# VRAM_SIMM_TC5262x7J_v1_0_Sch_EasyEDA.net
KiCad netlist of a schematic drawn in EasyEDA
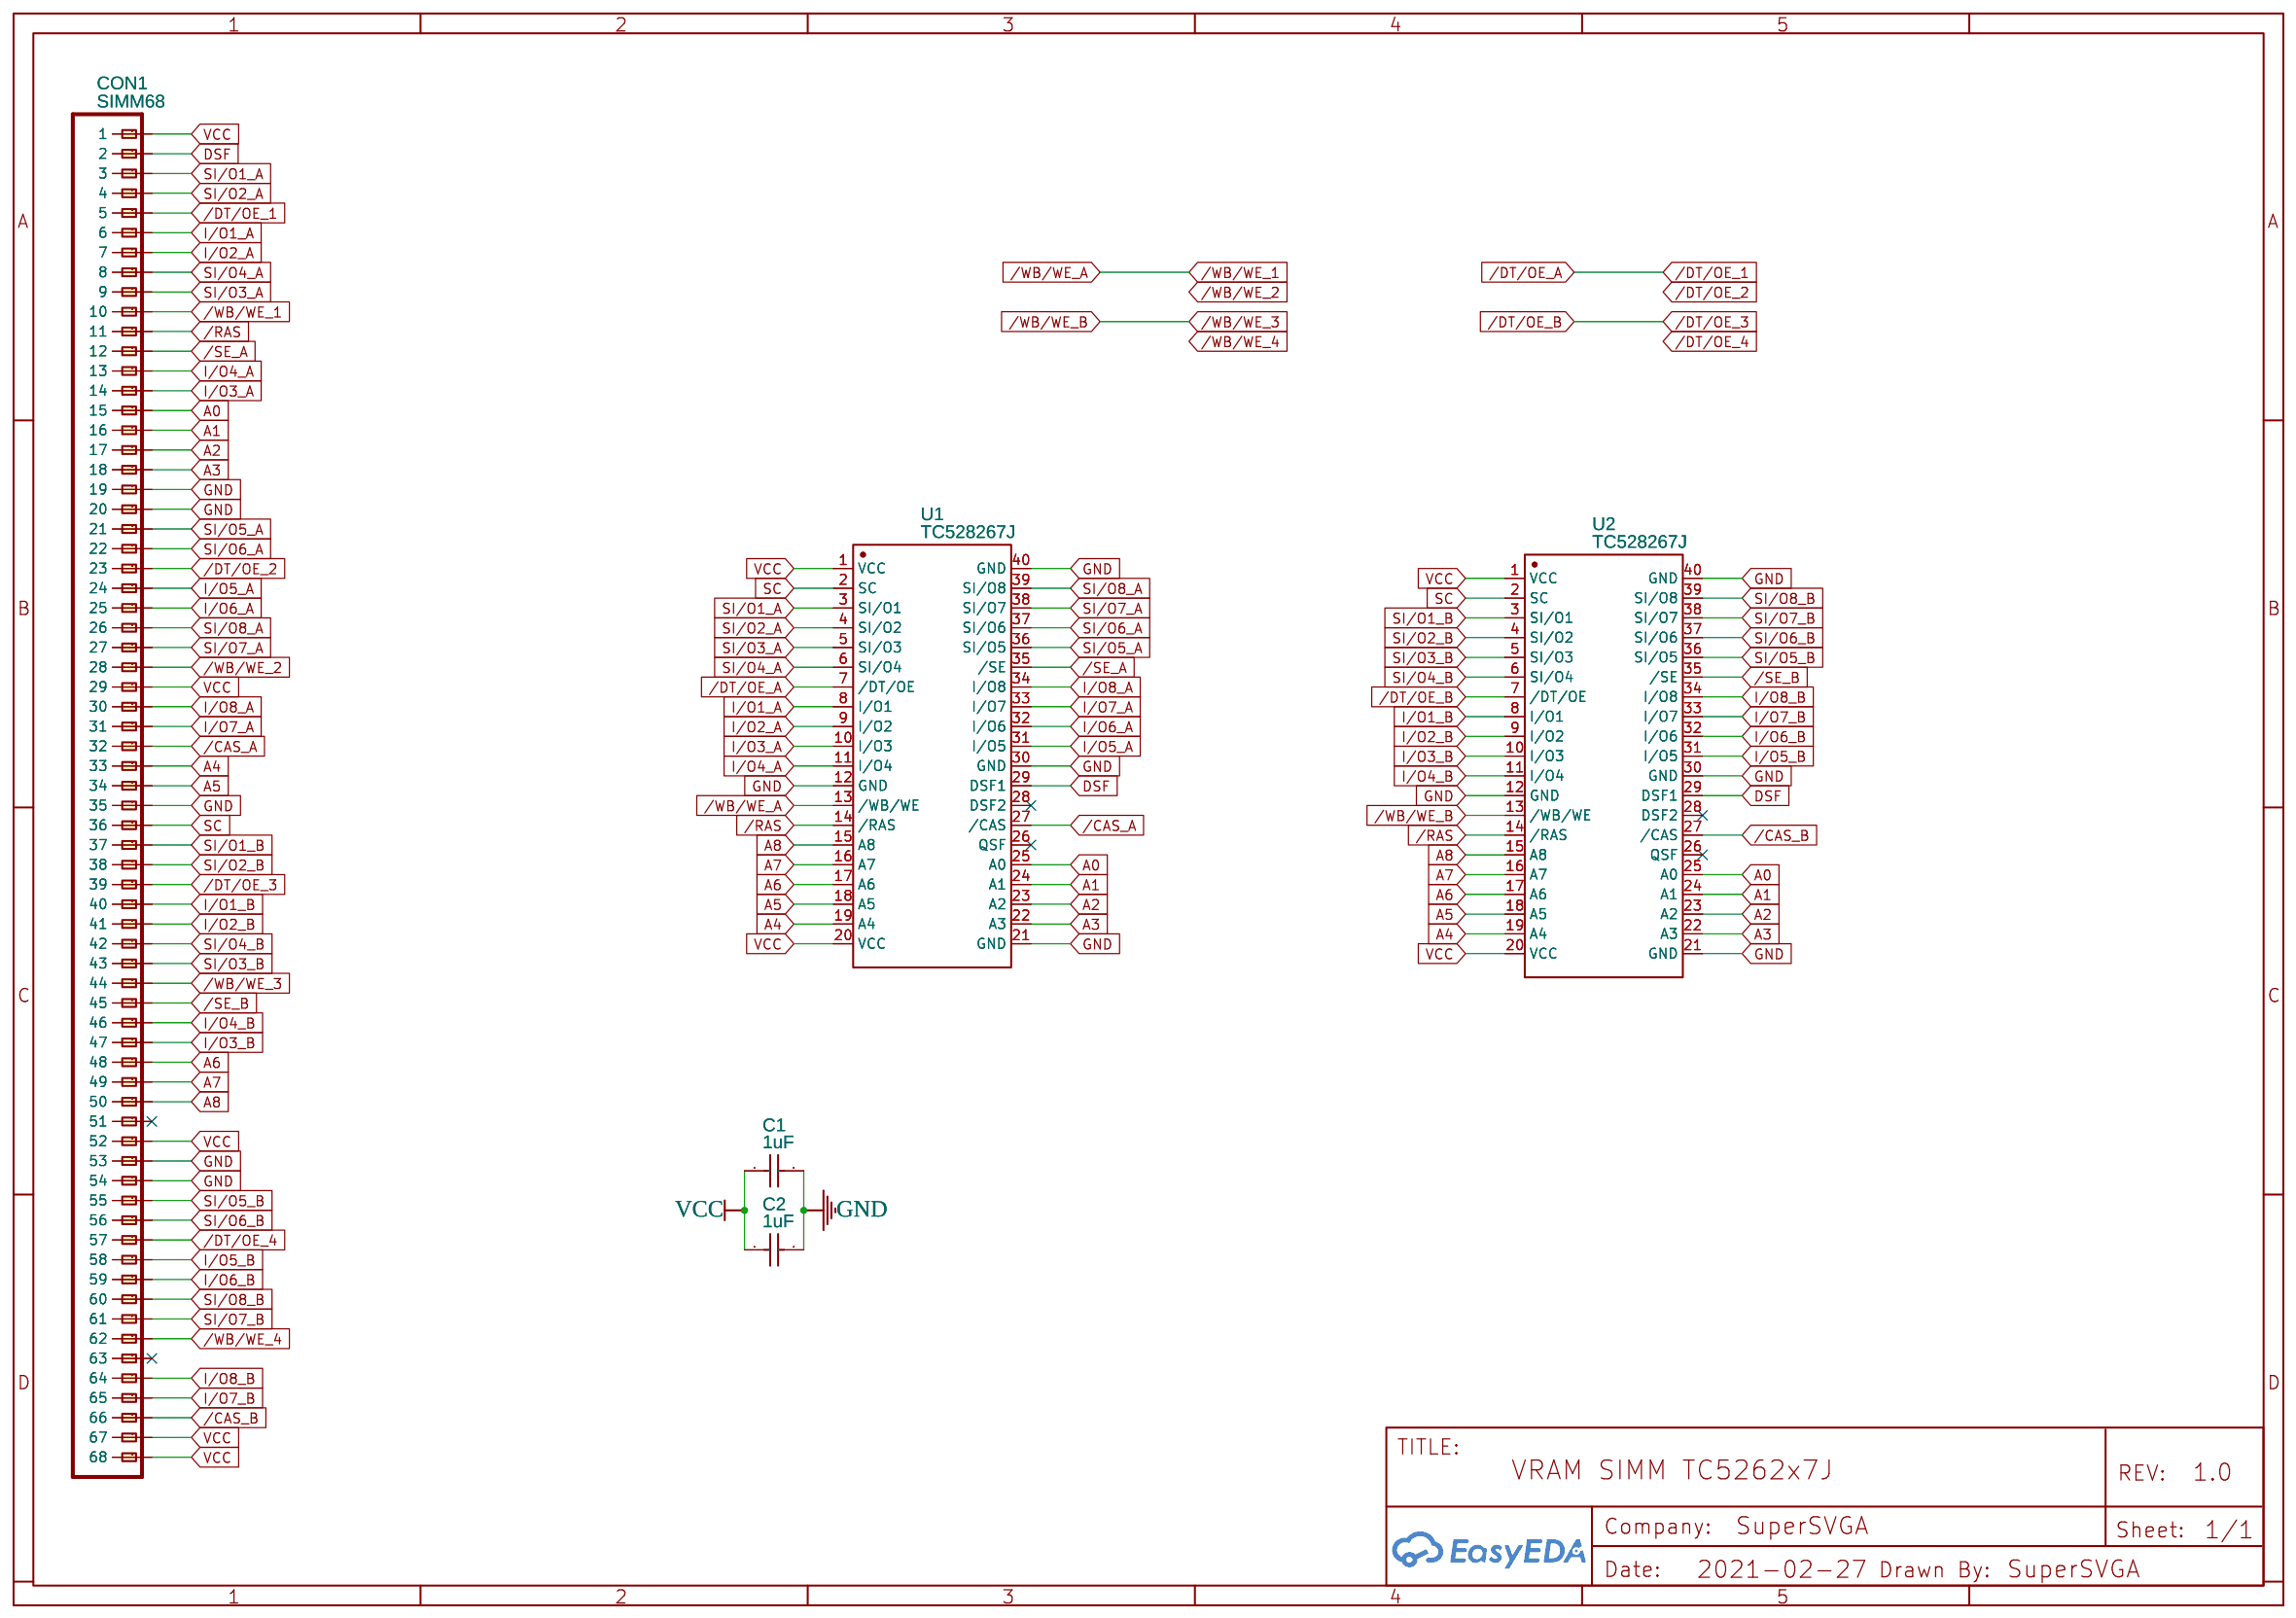
[diagram p0: schematic sheet]

(export (version "E")
  (design (tool "Eeschema 10.0.6"))
  (components
    (comp (ref "C1")
      (value "1uF")
      (fields
        (field (name "BOM_Manufacturer Part") "CL10A105KP8NNNC")
        (field (name "BOM_Supplier Part") "C26413")
      )
      (libsource (lib "") (part "CL10A105KP8NNNC"))
    )
    (comp (ref "C2")
      (value "1uF")
      (fields
        (field (name "BOM_Manufacturer Part") "CL10A105KP8NNNC")
        (field (name "BOM_Supplier Part") "C26413")
      )
      (libsource (lib "") (part "CL10A105KP8NNNC"))
    )
    (comp (ref "CON1") (value "SIMM68") (libsource (lib "") (part "SIMM68")))
    (comp (ref "U1") (value "TC528267J") (libsource (lib "") (part "TC528267J")))
    (comp (ref "U2") (value "TC528267J") (libsource (lib "") (part "TC528267J")))
  )
  (nets
    (net (code "1") (name "A0") (class "Default")
      (node (ref "CON1") (pin "15") (pinfunction "15_15") (pintype "unspecified"))
      (node (ref "U1") (pin "25") (pinfunction "A0_25") (pintype "input"))
      (node (ref "U2") (pin "25") (pinfunction "A0_25") (pintype "input"))
    )
    (net (code "2") (name "A1") (class "Default")
      (node (ref "CON1") (pin "16") (pinfunction "16_16") (pintype "unspecified"))
      (node (ref "U1") (pin "24") (pinfunction "A1_24") (pintype "input"))
      (node (ref "U2") (pin "24") (pinfunction "A1_24") (pintype "input"))
    )
    (net (code "3") (name "A2") (class "Default")
      (node (ref "CON1") (pin "17") (pinfunction "17_17") (pintype "unspecified"))
      (node (ref "U1") (pin "23") (pinfunction "A2_23") (pintype "input"))
      (node (ref "U2") (pin "23") (pinfunction "A2_23") (pintype "input"))
    )
    (net (code "4") (name "A3") (class "Default")
      (node (ref "CON1") (pin "18") (pinfunction "18_18") (pintype "unspecified"))
      (node (ref "U1") (pin "22") (pinfunction "A3_22") (pintype "input"))
      (node (ref "U2") (pin "22") (pinfunction "A3_22") (pintype "input"))
    )
    (net (code "5") (name "A4") (class "Default")
      (node (ref "CON1") (pin "33") (pinfunction "33_33") (pintype "unspecified"))
      (node (ref "U1") (pin "19") (pinfunction "A4_19") (pintype "input"))
      (node (ref "U2") (pin "19") (pinfunction "A4_19") (pintype "input"))
    )
    (net (code "6") (name "A5") (class "Default")
      (node (ref "CON1") (pin "34") (pinfunction "34_34") (pintype "unspecified"))
      (node (ref "U1") (pin "18") (pinfunction "A5_18") (pintype "input"))
      (node (ref "U2") (pin "18") (pinfunction "A5_18") (pintype "input"))
    )
    (net (code "7") (name "A6") (class "Default")
      (node (ref "CON1") (pin "48") (pinfunction "48_48") (pintype "unspecified"))
      (node (ref "U1") (pin "17") (pinfunction "A6_17") (pintype "input"))
      (node (ref "U2") (pin "17") (pinfunction "A6_17") (pintype "input"))
    )
    (net (code "8") (name "A7") (class "Default")
      (node (ref "CON1") (pin "49") (pinfunction "49_49") (pintype "unspecified"))
      (node (ref "U1") (pin "16") (pinfunction "A7_16") (pintype "input"))
      (node (ref "U2") (pin "16") (pinfunction "A7_16") (pintype "input"))
    )
    (net (code "9") (name "A8") (class "Default")
      (node (ref "CON1") (pin "50") (pinfunction "50_50") (pintype "unspecified"))
      (node (ref "U1") (pin "15") (pinfunction "A8_15") (pintype "input"))
      (node (ref "U2") (pin "15") (pinfunction "A8_15") (pintype "input"))
    )
    (net (code "10") (name "DSF") (class "Default")
      (node (ref "CON1") (pin "2") (pinfunction "2_2") (pintype "unspecified"))
      (node (ref "U1") (pin "29") (pinfunction "DSF1_29") (pintype "input"))
      (node (ref "U2") (pin "29") (pinfunction "DSF1_29") (pintype "input"))
    )
    (net (code "11") (name "GND") (class "Default")
      (node (ref "C1") (pin "2") (pinfunction "2_2") (pintype "input"))
      (node (ref "C2") (pin "2") (pinfunction "2_2") (pintype "input"))
      (node (ref "CON1") (pin "19") (pinfunction "19_19") (pintype "unspecified"))
      (node (ref "CON1") (pin "20") (pinfunction "20_20") (pintype "unspecified"))
      (node (ref "CON1") (pin "35") (pinfunction "35_35") (pintype "unspecified"))
      (node (ref "CON1") (pin "53") (pinfunction "53_53") (pintype "unspecified"))
      (node (ref "CON1") (pin "54") (pinfunction "54_54") (pintype "unspecified"))
      (node (ref "U1") (pin "12") (pinfunction "GND_12") (pintype "passive"))
      (node (ref "U1") (pin "21") (pinfunction "GND_21") (pintype "passive"))
      (node (ref "U1") (pin "30") (pinfunction "GND_30") (pintype "passive"))
      (node (ref "U1") (pin "40") (pinfunction "GND_40") (pintype "passive"))
      (node (ref "U2") (pin "12") (pinfunction "GND_12") (pintype "passive"))
      (node (ref "U2") (pin "21") (pinfunction "GND_21") (pintype "passive"))
      (node (ref "U2") (pin "30") (pinfunction "GND_30") (pintype "passive"))
      (node (ref "U2") (pin "40") (pinfunction "GND_40") (pintype "passive"))
    )
    (net (code "12") (name "I{slash}O1_A") (class "Default")
      (node (ref "CON1") (pin "6") (pinfunction "6_6") (pintype "unspecified"))
      (node (ref "U1") (pin "8") (pinfunction "I/O1_8") (pintype "bidirectional"))
    )
    (net (code "13") (name "I{slash}O1_B") (class "Default")
      (node (ref "CON1") (pin "40") (pinfunction "40_40") (pintype "unspecified"))
      (node (ref "U2") (pin "8") (pinfunction "I/O1_8") (pintype "bidirectional"))
    )
    (net (code "14") (name "I{slash}O2_A") (class "Default")
      (node (ref "CON1") (pin "7") (pinfunction "7_7") (pintype "unspecified"))
      (node (ref "U1") (pin "9") (pinfunction "I/O2_9") (pintype "bidirectional"))
    )
    (net (code "15") (name "I{slash}O2_B") (class "Default")
      (node (ref "CON1") (pin "41") (pinfunction "41_41") (pintype "unspecified"))
      (node (ref "U2") (pin "9") (pinfunction "I/O2_9") (pintype "bidirectional"))
    )
    (net (code "16") (name "I{slash}O3_A") (class "Default")
      (node (ref "CON1") (pin "14") (pinfunction "14_14") (pintype "unspecified"))
      (node (ref "U1") (pin "10") (pinfunction "I/O3_10") (pintype "bidirectional"))
    )
    (net (code "17") (name "I{slash}O3_B") (class "Default")
      (node (ref "CON1") (pin "47") (pinfunction "47_47") (pintype "unspecified"))
      (node (ref "U2") (pin "10") (pinfunction "I/O3_10") (pintype "bidirectional"))
    )
    (net (code "18") (name "I{slash}O4_A") (class "Default")
      (node (ref "CON1") (pin "13") (pinfunction "13_13") (pintype "unspecified"))
      (node (ref "U1") (pin "11") (pinfunction "I/O4_11") (pintype "bidirectional"))
    )
    (net (code "19") (name "I{slash}O4_B") (class "Default")
      (node (ref "CON1") (pin "46") (pinfunction "46_46") (pintype "unspecified"))
      (node (ref "U2") (pin "11") (pinfunction "I/O4_11") (pintype "bidirectional"))
    )
    (net (code "20") (name "I{slash}O5_A") (class "Default")
      (node (ref "CON1") (pin "24") (pinfunction "24_24") (pintype "unspecified"))
      (node (ref "U1") (pin "31") (pinfunction "I/O5_31") (pintype "bidirectional"))
    )
    (net (code "21") (name "I{slash}O5_B") (class "Default")
      (node (ref "CON1") (pin "58") (pinfunction "58_58") (pintype "unspecified"))
      (node (ref "U2") (pin "31") (pinfunction "I/O5_31") (pintype "bidirectional"))
    )
    (net (code "22") (name "I{slash}O6_A") (class "Default")
      (node (ref "CON1") (pin "25") (pinfunction "25_25") (pintype "unspecified"))
      (node (ref "U1") (pin "32") (pinfunction "I/O6_32") (pintype "bidirectional"))
    )
    (net (code "23") (name "I{slash}O6_B") (class "Default")
      (node (ref "CON1") (pin "59") (pinfunction "59_59") (pintype "unspecified"))
      (node (ref "U2") (pin "32") (pinfunction "I/O6_32") (pintype "bidirectional"))
    )
    (net (code "24") (name "I{slash}O7_A") (class "Default")
      (node (ref "CON1") (pin "31") (pinfunction "31_31") (pintype "unspecified"))
      (node (ref "U1") (pin "33") (pinfunction "I/O7_33") (pintype "bidirectional"))
    )
    (net (code "25") (name "I{slash}O7_B") (class "Default")
      (node (ref "CON1") (pin "65") (pinfunction "65_65") (pintype "unspecified"))
      (node (ref "U2") (pin "33") (pinfunction "I/O7_33") (pintype "bidirectional"))
    )
    (net (code "26") (name "I{slash}O8_A") (class "Default")
      (node (ref "CON1") (pin "30") (pinfunction "30_30") (pintype "unspecified"))
      (node (ref "U1") (pin "34") (pinfunction "I/O8_34") (pintype "bidirectional"))
    )
    (net (code "27") (name "I{slash}O8_B") (class "Default")
      (node (ref "CON1") (pin "64") (pinfunction "64_64") (pintype "unspecified"))
      (node (ref "U2") (pin "34") (pinfunction "I/O8_34") (pintype "bidirectional"))
    )
    (net (code "28") (name "SC") (class "Default")
      (node (ref "CON1") (pin "36") (pinfunction "36_36") (pintype "unspecified"))
      (node (ref "U1") (pin "2") (pinfunction "SC_2") (pintype "input"))
      (node (ref "U2") (pin "2") (pinfunction "SC_2") (pintype "input"))
    )
    (net (code "29") (name "SI{slash}O1_A") (class "Default")
      (node (ref "CON1") (pin "3") (pinfunction "3_3") (pintype "unspecified"))
      (node (ref "U1") (pin "3") (pinfunction "SI/O1_3") (pintype "bidirectional"))
    )
    (net (code "30") (name "SI{slash}O1_B") (class "Default")
      (node (ref "CON1") (pin "37") (pinfunction "37_37") (pintype "unspecified"))
      (node (ref "U2") (pin "3") (pinfunction "SI/O1_3") (pintype "bidirectional"))
    )
    (net (code "31") (name "SI{slash}O2_A") (class "Default")
      (node (ref "CON1") (pin "4") (pinfunction "4_4") (pintype "unspecified"))
      (node (ref "U1") (pin "4") (pinfunction "SI/O2_4") (pintype "bidirectional"))
    )
    (net (code "32") (name "SI{slash}O2_B") (class "Default")
      (node (ref "CON1") (pin "38") (pinfunction "38_38") (pintype "unspecified"))
      (node (ref "U2") (pin "4") (pinfunction "SI/O2_4") (pintype "bidirectional"))
    )
    (net (code "33") (name "SI{slash}O3_A") (class "Default")
      (node (ref "CON1") (pin "9") (pinfunction "9_9") (pintype "unspecified"))
      (node (ref "U1") (pin "5") (pinfunction "SI/O3_5") (pintype "bidirectional"))
    )
    (net (code "34") (name "SI{slash}O3_B") (class "Default")
      (node (ref "CON1") (pin "43") (pinfunction "43_43") (pintype "unspecified"))
      (node (ref "U2") (pin "5") (pinfunction "SI/O3_5") (pintype "bidirectional"))
    )
    (net (code "35") (name "SI{slash}O4_A") (class "Default")
      (node (ref "CON1") (pin "8") (pinfunction "8_8") (pintype "unspecified"))
      (node (ref "U1") (pin "6") (pinfunction "SI/O4_6") (pintype "bidirectional"))
    )
    (net (code "36") (name "SI{slash}O4_B") (class "Default")
      (node (ref "CON1") (pin "42") (pinfunction "42_42") (pintype "unspecified"))
      (node (ref "U2") (pin "6") (pinfunction "SI/O4_6") (pintype "bidirectional"))
    )
    (net (code "37") (name "SI{slash}O5_A") (class "Default")
      (node (ref "CON1") (pin "21") (pinfunction "21_21") (pintype "unspecified"))
      (node (ref "U1") (pin "36") (pinfunction "SI/O5_36") (pintype "bidirectional"))
    )
    (net (code "38") (name "SI{slash}O5_B") (class "Default")
      (node (ref "CON1") (pin "55") (pinfunction "55_55") (pintype "unspecified"))
      (node (ref "U2") (pin "36") (pinfunction "SI/O5_36") (pintype "bidirectional"))
    )
    (net (code "39") (name "SI{slash}O6_A") (class "Default")
      (node (ref "CON1") (pin "22") (pinfunction "22_22") (pintype "unspecified"))
      (node (ref "U1") (pin "37") (pinfunction "SI/O6_37") (pintype "bidirectional"))
    )
    (net (code "40") (name "SI{slash}O6_B") (class "Default")
      (node (ref "CON1") (pin "56") (pinfunction "56_56") (pintype "unspecified"))
      (node (ref "U2") (pin "37") (pinfunction "SI/O6_37") (pintype "bidirectional"))
    )
    (net (code "41") (name "SI{slash}O7_A") (class "Default")
      (node (ref "CON1") (pin "27") (pinfunction "27_27") (pintype "unspecified"))
      (node (ref "U1") (pin "38") (pinfunction "SI/O7_38") (pintype "bidirectional"))
    )
    (net (code "42") (name "SI{slash}O7_B") (class "Default")
      (node (ref "CON1") (pin "61") (pinfunction "61_61") (pintype "unspecified"))
      (node (ref "U2") (pin "38") (pinfunction "SI/O7_38") (pintype "bidirectional"))
    )
    (net (code "43") (name "SI{slash}O8_A") (class "Default")
      (node (ref "CON1") (pin "26") (pinfunction "26_26") (pintype "unspecified"))
      (node (ref "U1") (pin "39") (pinfunction "SI/O8_39") (pintype "bidirectional"))
    )
    (net (code "44") (name "SI{slash}O8_B") (class "Default")
      (node (ref "CON1") (pin "60") (pinfunction "60_60") (pintype "unspecified"))
      (node (ref "U2") (pin "39") (pinfunction "SI/O8_39") (pintype "bidirectional"))
    )
    (net (code "45") (name "VCC") (class "Default")
      (node (ref "C1") (pin "1") (pinfunction "1_1") (pintype "input"))
      (node (ref "C2") (pin "1") (pinfunction "1_1") (pintype "input"))
      (node (ref "CON1") (pin "1") (pinfunction "1_1") (pintype "unspecified"))
      (node (ref "CON1") (pin "29") (pinfunction "29_29") (pintype "unspecified"))
      (node (ref "CON1") (pin "52") (pinfunction "52_52") (pintype "unspecified"))
      (node (ref "CON1") (pin "67") (pinfunction "67_67") (pintype "unspecified"))
      (node (ref "CON1") (pin "68") (pinfunction "68_68") (pintype "unspecified"))
      (node (ref "U1") (pin "1") (pinfunction "VCC_1") (pintype "passive"))
      (node (ref "U1") (pin "20") (pinfunction "VCC_20") (pintype "passive"))
      (node (ref "U2") (pin "1") (pinfunction "VCC_1") (pintype "passive"))
      (node (ref "U2") (pin "20") (pinfunction "VCC_20") (pintype "passive"))
    )
    (net (code "46") (name "unconnected-(CON1-Pad51)") (class "Default")
      (node (ref "CON1") (pin "51") (pinfunction "51_51") (pintype "unspecified+no_connect"))
    )
    (net (code "47") (name "unconnected-(CON1-Pad63)") (class "Default")
      (node (ref "CON1") (pin "63") (pinfunction "63_63") (pintype "unspecified+no_connect"))
    )
    (net (code "48") (name "unconnected-(U1-DSF2-Pad28)") (class "Default")
      (node (ref "U1") (pin "28") (pinfunction "DSF2_28") (pintype "input+no_connect"))
    )
    (net (code "49") (name "unconnected-(U1-QSF-Pad26)") (class "Default")
      (node (ref "U1") (pin "26") (pinfunction "QSF_26") (pintype "input+no_connect"))
    )
    (net (code "50") (name "unconnected-(U2-DSF2-Pad28)") (class "Default")
      (node (ref "U2") (pin "28") (pinfunction "DSF2_28") (pintype "input+no_connect"))
    )
    (net (code "51") (name "unconnected-(U2-QSF-Pad26)") (class "Default")
      (node (ref "U2") (pin "26") (pinfunction "QSF_26") (pintype "input+no_connect"))
    )
    (net (code "52") (name "{slash}CAS_A") (class "Default")
      (node (ref "CON1") (pin "32") (pinfunction "32_32") (pintype "unspecified"))
      (node (ref "U1") (pin "27") (pinfunction "/CAS_27") (pintype "input"))
    )
    (net (code "53") (name "{slash}CAS_B") (class "Default")
      (node (ref "CON1") (pin "66") (pinfunction "66_66") (pintype "unspecified"))
      (node (ref "U2") (pin "27") (pinfunction "/CAS_27") (pintype "input"))
    )
    (net (code "54") (name "{slash}DT{slash}OE_1") (class "Default")
      (node (ref "CON1") (pin "5") (pinfunction "5_5") (pintype "unspecified"))
      (node (ref "U1") (pin "7") (pinfunction "/DT/OE_7") (pintype "input"))
    )
    (net (code "55") (name "{slash}DT{slash}OE_2") (class "Default")
      (node (ref "CON1") (pin "23") (pinfunction "23_23") (pintype "unspecified"))
    )
    (net (code "56") (name "{slash}DT{slash}OE_3") (class "Default")
      (node (ref "CON1") (pin "39") (pinfunction "39_39") (pintype "unspecified"))
      (node (ref "U2") (pin "7") (pinfunction "/DT/OE_7") (pintype "input"))
    )
    (net (code "57") (name "{slash}DT{slash}OE_4") (class "Default")
      (node (ref "CON1") (pin "57") (pinfunction "57_57") (pintype "unspecified"))
    )
    (net (code "58") (name "{slash}RAS") (class "Default")
      (node (ref "CON1") (pin "11") (pinfunction "11_11") (pintype "unspecified"))
      (node (ref "U1") (pin "14") (pinfunction "/RAS_14") (pintype "input"))
      (node (ref "U2") (pin "14") (pinfunction "/RAS_14") (pintype "input"))
    )
    (net (code "59") (name "{slash}SE_A") (class "Default")
      (node (ref "CON1") (pin "12") (pinfunction "12_12") (pintype "unspecified"))
      (node (ref "U1") (pin "35") (pinfunction "/SE_35") (pintype "input"))
    )
    (net (code "60") (name "{slash}SE_B") (class "Default")
      (node (ref "CON1") (pin "45") (pinfunction "45_45") (pintype "unspecified"))
      (node (ref "U2") (pin "35") (pinfunction "/SE_35") (pintype "input"))
    )
    (net (code "61") (name "{slash}WB{slash}WE_1") (class "Default")
      (node (ref "CON1") (pin "10") (pinfunction "10_10") (pintype "unspecified"))
      (node (ref "U1") (pin "13") (pinfunction "/WB/WE_13") (pintype "input"))
    )
    (net (code "62") (name "{slash}WB{slash}WE_2") (class "Default")
      (node (ref "CON1") (pin "28") (pinfunction "28_28") (pintype "unspecified"))
    )
    (net (code "63") (name "{slash}WB{slash}WE_3") (class "Default")
      (node (ref "CON1") (pin "44") (pinfunction "44_44") (pintype "unspecified"))
      (node (ref "U2") (pin "13") (pinfunction "/WB/WE_13") (pintype "input"))
    )
    (net (code "64") (name "{slash}WB{slash}WE_4") (class "Default")
      (node (ref "CON1") (pin "62") (pinfunction "62_62") (pintype "unspecified"))
    )
  )
)
